# MCU.net
KiCad netlist of a schematic drawn in Altium Designer
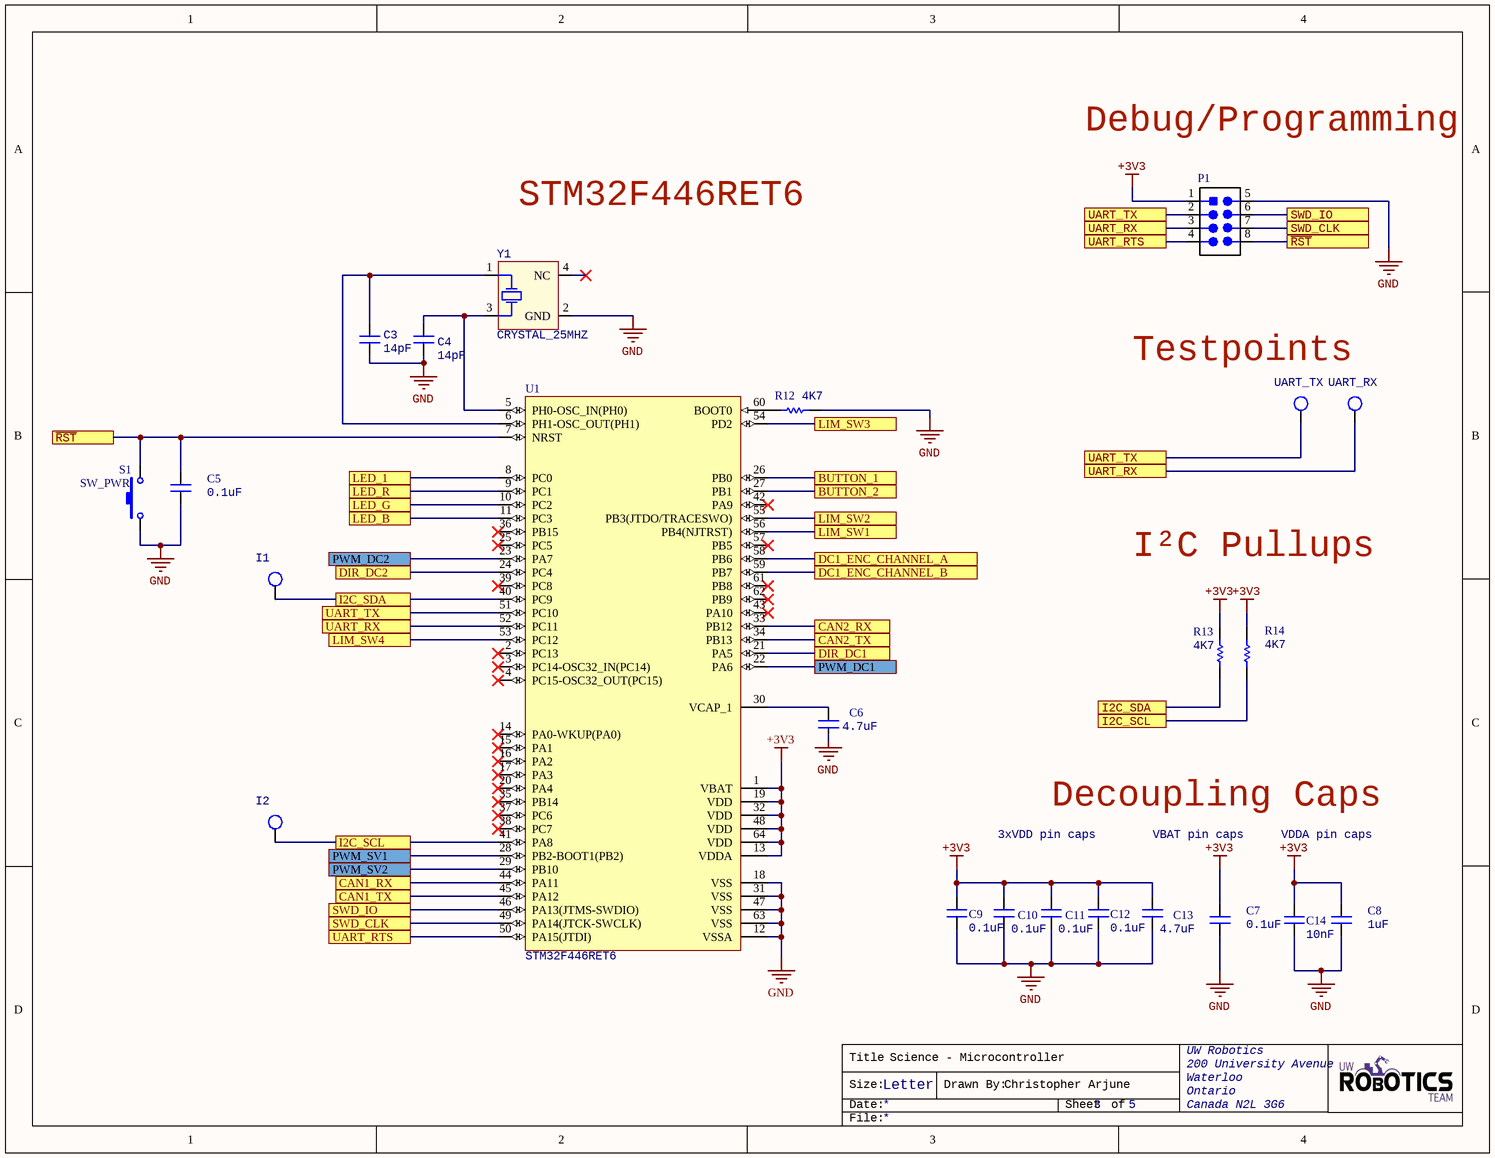
[diagram p0: MCU.SchDoc]

(export (version "E")
  (design (tool "Eeschema 10.0.6"))
  (components
    (comp (ref "C3")
      (value "14pF")
      (description "CAP CER 14PF 50V C0G/NP0 0603")
      (fields (field (name "TOLERANCE") "5%") (field (name "Comment") "CAP_14pF_50V_0603"))
      (libsource (lib "UWRT_Schematic_Library_2020") (part "CAP_14pF_50V_0603"))
    )
    (comp (ref "C4")
      (value "14pF")
      (description "CAP CER 14PF 50V C0G/NP0 0603")
      (fields (field (name "TOLERANCE") "5%") (field (name "Comment") "CAP_14pF_50V_0603"))
      (libsource (lib "UWRT_Schematic_Library_2020") (part "CAP_14pF_50V_0603"))
    )
    (comp (ref "C5")
      (value "0.1uF")
      (footprint "CAPC0603(1608)55_N")
      (description "CAP CER 0.1UF 16V X7R 0603")
      (fields (field (name "MANUFACTURER") "Yageo") (field (name "MPN") "CC0603KRX7R7BB104"))
      (libsource (lib "UWRT_Schematic_Library_2020") (part "CAP_0.1uF_16V_0603"))
    )
    (comp (ref "C6")
      (value "4.7uF")
      (footprint "CAPC0603(1608)55_N")
      (description "CAP CER 4.7UF 6.3V X5R 0603")
      (fields (field (name "MANUFACTURER") "Yageo") (field (name "MPN") "CC0603KRX5R5BB475"))
      (libsource (lib "UWRT_Schematic_Library_2020") (part "CAP_4.7uF_0603"))
    )
    (comp (ref "C7")
      (value "0.1uF")
      (footprint "CAPC0603(1608)55_N")
      (description "CAP CER 0.1UF 16V X7R 0603")
      (fields (field (name "MANUFACTURER") "Yageo") (field (name "MPN") "CC0603KRX7R7BB104"))
      (libsource (lib "UWRT_Schematic_Library_2020") (part "CAP_0.1uF_16V_0603"))
    )
    (comp (ref "C8")
      (value "1uF")
      (footprint "CAPC0603(1608)55_N")
      (description "CAP CER 1UF 16V Y5V 0603")
      (fields (field (name "MANUFACTURER") "Yageo") (field (name "MPN") "CC0603ZRY5V7BB105"))
      (libsource (lib "UWRT_Schematic_Library_2020") (part "CAP_1uF_16V_0603"))
    )
    (comp (ref "C9")
      (value "0.1uF")
      (footprint "CAPC0603(1608)55_N")
      (description "CAP CER 0.1UF 16V X7R 0603")
      (fields (field (name "MANUFACTURER") "Yageo") (field (name "MPN") "CC0603KRX7R7BB104"))
      (libsource (lib "UWRT_Schematic_Library_2020") (part "CAP_0.1uF_16V_0603"))
    )
    (comp (ref "C10")
      (value "0.1uF")
      (footprint "CAPC0603(1608)55_N")
      (description "CAP CER 0.1UF 16V X7R 0603")
      (fields (field (name "MANUFACTURER") "Yageo") (field (name "MPN") "CC0603KRX7R7BB104"))
      (libsource (lib "UWRT_Schematic_Library_2020") (part "CAP_0.1uF_16V_0603"))
    )
    (comp (ref "C11")
      (value "0.1uF")
      (footprint "CAPC0603(1608)55_N")
      (description "CAP CER 0.1UF 16V X7R 0603")
      (fields (field (name "MANUFACTURER") "Yageo") (field (name "MPN") "CC0603KRX7R7BB104"))
      (libsource (lib "UWRT_Schematic_Library_2020") (part "CAP_0.1uF_16V_0603"))
    )
    (comp (ref "C12")
      (value "0.1uF")
      (footprint "CAPC0603(1608)55_N")
      (description "CAP CER 0.1UF 16V X7R 0603")
      (fields (field (name "MANUFACTURER") "Yageo") (field (name "MPN") "CC0603KRX7R7BB104"))
      (libsource (lib "UWRT_Schematic_Library_2020") (part "CAP_0.1uF_16V_0603"))
    )
    (comp (ref "C13")
      (value "4.7uF")
      (footprint "CAPC0603(1608)55_N")
      (description "CAP CER 4.7UF 6.3V X5R 0603")
      (fields (field (name "MANUFACTURER") "Yageo") (field (name "MPN") "CC0603KRX5R5BB475"))
      (libsource (lib "UWRT_Schematic_Library_2020") (part "CAP_4.7uF_0603"))
    )
    (comp (ref "C14")
      (value "10nF")
      (footprint "CAPC0603(1608)55_N")
      (description "CAP CER 10000PF 16V X7R 0603")
      (fields (field (name "MANUFACTURER") "Yageo") (field (name "MPN") "CC0603KRX7R7BB103"))
      (libsource (lib "UWRT_Schematic_Library_2020") (part "CAP_10nF_0603"))
    )
    (comp (ref "I1")
      (value "TESTPOINT_LOOP")
      (footprint "TESTPOINT_LOOP")
      (description "Loop testpoint through-hole pad")
      (fields (field (name "MANUFACTURER") "Keystone Electronics"))
      (libsource (lib "UWRT_Schematic_Library_2020") (part "TESTPOINT_LOOP"))
    )
    (comp (ref "I2")
      (value "TESTPOINT_LOOP")
      (footprint "TESTPOINT_LOOP")
      (description "Loop testpoint through-hole pad")
      (fields (field (name "MANUFACTURER") "Keystone Electronics"))
      (libsource (lib "UWRT_Schematic_Library_2020") (part "TESTPOINT_LOOP"))
    )
    (comp (ref "P1")
      (value "HEADER 4X2")
      (footprint "HEADER_2X4")
      (description "CONN HEADER VERT 8POS 2.54MM")
      (libsource (lib "UWRT_Schematic_Library_2020") (part "HEADER 4X2"))
    )
    (comp (ref "R12")
      (value "4K7")
      (footprint "RESC0603(1608)_N")
      (description "RES SMD 4.7K OHM 5% 1/10W 0603")
      (fields (field (name "MANUFACTURER") "Yageo") (field (name "TOLERANCE") "5%"))
      (libsource (lib "UWRT_Schematic_Library_2020") (part "RES_4K7_0603"))
    )
    (comp (ref "R13")
      (value "4K7")
      (footprint "RESC0603(1608)_N")
      (description "RES SMD 4.7K OHM 5% 1/10W 0603")
      (fields (field (name "MANUFACTURER") "Yageo") (field (name "TOLERANCE") "5%"))
      (libsource (lib "UWRT_Schematic_Library_2020") (part "RES_4K7_0603"))
    )
    (comp (ref "R14")
      (value "4K7")
      (footprint "RESC0603(1608)_N")
      (description "RES SMD 4.7K OHM 5% 1/10W 0603")
      (fields (field (name "MANUFACTURER") "Yageo") (field (name "TOLERANCE") "5%"))
      (libsource (lib "UWRT_Schematic_Library_2020") (part "RES_4K7_0603"))
    )
    (comp (ref "S1")
      (value "SW_PWR")
      (footprint "PTS830GM140")
      (description "Power Switch (Red)")
      (fields (field (name "MPN") "PTS830GM140 SMTR LFS") (field (name "MANUFACTURER") "C&K"))
      (libsource (lib "UWRT_Schematic_Library_2020") (part "SW_PWR"))
    )
    (comp (ref "U1")
      (value "STM32F446RET6")
      (footprint "STM-LQFP64_L")
      (libsource (lib "UWRT_Schematic_Library_2020") (part "MCU_STM32F446RET6"))
    )
    (comp (ref "UART_RX")
      (value "TESTPOINT_LOOP")
      (footprint "TESTPOINT_LOOP")
      (description "Loop testpoint through-hole pad")
      (fields (field (name "MANUFACTURER") "Keystone Electronics"))
      (libsource (lib "UWRT_Schematic_Library_2020") (part "TESTPOINT_LOOP"))
    )
    (comp (ref "UART_TX")
      (value "TESTPOINT_LOOP")
      (footprint "TESTPOINT_LOOP")
      (description "Loop testpoint through-hole pad")
      (fields (field (name "MANUFACTURER") "Keystone Electronics"))
      (libsource (lib "UWRT_Schematic_Library_2020") (part "TESTPOINT_LOOP"))
    )
    (comp (ref "Y1")
      (value "CRYSTAL_25MHZ")
      (description "CRYSTAL 25.0000MHZ 12PF SMD")
      (libsource (lib "UWRT_Schematic_Library_2020") (part "CRYSTAL_25MHZ"))
    )
  )
  (nets
    (net (code "1") (name "+3V3") (class "Default")
      (node (ref "C10") (pin "2") (pinfunction "2_2") (pintype "passive"))
      (node (ref "C11") (pin "2") (pinfunction "2_2") (pintype "passive"))
      (node (ref "C12") (pin "2") (pinfunction "2_2") (pintype "passive"))
      (node (ref "C13") (pin "2") (pinfunction "2_2") (pintype "passive"))
      (node (ref "C14") (pin "2") (pinfunction "2_2") (pintype "passive"))
      (node (ref "C7") (pin "2") (pinfunction "2_2") (pintype "passive"))
      (node (ref "C8") (pin "2") (pinfunction "2_2") (pintype "passive"))
      (node (ref "C9") (pin "2") (pinfunction "2_2") (pintype "passive"))
      (node (ref "P1") (pin "1") (pinfunction "VCC_1") (pintype "passive"))
      (node (ref "R13") (pin "2") (pinfunction "2_2") (pintype "passive"))
      (node (ref "R14") (pin "2") (pinfunction "2_2") (pintype "passive"))
      (node (ref "U1") (pin "1") (pinfunction "VBAT_1") (pintype "power_in"))
      (node (ref "U1") (pin "13") (pinfunction "VDDA_13") (pintype "power_in"))
      (node (ref "U1") (pin "19") (pinfunction "VDD_19") (pintype "power_in"))
      (node (ref "U1") (pin "32") (pinfunction "VDD_32") (pintype "power_in"))
      (node (ref "U1") (pin "48") (pinfunction "VDD_48") (pintype "power_in"))
      (node (ref "U1") (pin "64") (pinfunction "VDD_64") (pintype "power_in"))
    )
    (net (code "2") (name "/BUTTON_1") (class "Default")
      (node (ref "U1") (pin "26") (pinfunction "PB0_26") (pintype "bidirectional"))
    )
    (net (code "3") (name "/BUTTON_2") (class "Default")
      (node (ref "U1") (pin "27") (pinfunction "PB1_27") (pintype "bidirectional"))
    )
    (net (code "4") (name "/CAN1_RX") (class "Default")
      (node (ref "U1") (pin "44") (pinfunction "PA11_44") (pintype "bidirectional"))
    )
    (net (code "5") (name "/CAN1_TX") (class "Default")
      (node (ref "U1") (pin "45") (pinfunction "PA12_45") (pintype "bidirectional"))
    )
    (net (code "6") (name "/CAN2_RX") (class "Default")
      (node (ref "U1") (pin "33") (pinfunction "PB12_33") (pintype "bidirectional"))
    )
    (net (code "7") (name "/CAN2_TX") (class "Default")
      (node (ref "U1") (pin "34") (pinfunction "PB13_34") (pintype "bidirectional"))
    )
    (net (code "8") (name "/DC1_ENC_CHANNEL_A") (class "Default")
      (node (ref "U1") (pin "58") (pinfunction "PB6_58") (pintype "bidirectional"))
    )
    (net (code "9") (name "/DC1_ENC_CHANNEL_B") (class "Default")
      (node (ref "U1") (pin "59") (pinfunction "PB7_59") (pintype "bidirectional"))
    )
    (net (code "10") (name "/DIR_DC1") (class "Default")
      (node (ref "U1") (pin "21") (pinfunction "PA5_21") (pintype "bidirectional"))
    )
    (net (code "11") (name "/DIR_DC2") (class "Default")
      (node (ref "U1") (pin "24") (pinfunction "PC4_24") (pintype "bidirectional"))
    )
    (net (code "12") (name "/I2C_SCL") (class "Default")
      (node (ref "I2") (pin "1") (pintype "passive"))
      (node (ref "R14") (pin "1") (pinfunction "1_1") (pintype "passive"))
      (node (ref "U1") (pin "41") (pinfunction "PA8_41") (pintype "bidirectional"))
    )
    (net (code "13") (name "/I2C_SDA") (class "Default")
      (node (ref "I1") (pin "1") (pintype "passive"))
      (node (ref "R13") (pin "1") (pinfunction "1_1") (pintype "passive"))
      (node (ref "U1") (pin "40") (pinfunction "PC9_40") (pintype "bidirectional"))
    )
    (net (code "14") (name "/LED_1") (class "Default")
      (node (ref "U1") (pin "8") (pinfunction "PC0_8") (pintype "bidirectional"))
    )
    (net (code "15") (name "/LED_B") (class "Default")
      (node (ref "U1") (pin "11") (pinfunction "PC3_11") (pintype "bidirectional"))
    )
    (net (code "16") (name "/LED_G") (class "Default")
      (node (ref "U1") (pin "10") (pinfunction "PC2_10") (pintype "bidirectional"))
    )
    (net (code "17") (name "/LED_R") (class "Default")
      (node (ref "U1") (pin "9") (pinfunction "PC1_9") (pintype "bidirectional"))
    )
    (net (code "18") (name "/LIM_SW1") (class "Default")
      (node (ref "U1") (pin "56") (pinfunction "PB4(NJTRST)_56") (pintype "bidirectional"))
    )
    (net (code "19") (name "/LIM_SW2") (class "Default")
      (node (ref "U1") (pin "55") (pinfunction "PB3(JTDO/TRACESWO)_55") (pintype "bidirectional"))
    )
    (net (code "20") (name "/LIM_SW3") (class "Default")
      (node (ref "U1") (pin "54") (pinfunction "PD2_54") (pintype "bidirectional"))
    )
    (net (code "21") (name "/LIM_SW4") (class "Default")
      (node (ref "U1") (pin "53") (pinfunction "PC12_53") (pintype "bidirectional"))
    )
    (net (code "22") (name "/PWM_DC1") (class "Default")
      (node (ref "U1") (pin "22") (pinfunction "PA6_22") (pintype "bidirectional"))
    )
    (net (code "23") (name "/PWM_DC2") (class "Default")
      (node (ref "U1") (pin "23") (pinfunction "PA7_23") (pintype "bidirectional"))
    )
    (net (code "24") (name "/PWM_SV1") (class "Default")
      (node (ref "U1") (pin "28") (pinfunction "PB2-BOOT1(PB2)_28") (pintype "bidirectional"))
    )
    (net (code "25") (name "/PWM_SV2") (class "Default")
      (node (ref "U1") (pin "29") (pinfunction "PB10_29") (pintype "bidirectional"))
    )
    (net (code "26") (name "/SWD_CLK") (class "Default")
      (node (ref "P1") (pin "7") (pinfunction "3_7") (pintype "passive"))
      (node (ref "U1") (pin "49") (pinfunction "PA14(JTCK-SWCLK)_49") (pintype "bidirectional"))
    )
    (net (code "27") (name "/SWD_IO") (class "Default")
      (node (ref "P1") (pin "6") (pinfunction "2_6") (pintype "passive"))
      (node (ref "U1") (pin "46") (pinfunction "PA13(JTMS-SWDIO)_46") (pintype "bidirectional"))
    )
    (net (code "28") (name "/UART_RTS") (class "Default")
      (node (ref "P1") (pin "4") (pinfunction "4_4") (pintype "passive"))
      (node (ref "U1") (pin "50") (pinfunction "PA15(JTDI)_50") (pintype "bidirectional"))
    )
    (net (code "29") (name "/UART_RX") (class "Default")
      (node (ref "P1") (pin "3") (pinfunction "3_3") (pintype "passive"))
      (node (ref "U1") (pin "52") (pinfunction "PC11_52") (pintype "bidirectional"))
      (node (ref "UART_RX") (pin "1") (pintype "passive"))
    )
    (net (code "30") (name "/UART_TX") (class "Default")
      (node (ref "P1") (pin "2") (pinfunction "2_2") (pintype "passive"))
      (node (ref "U1") (pin "51") (pinfunction "PC10_51") (pintype "bidirectional"))
      (node (ref "UART_TX") (pin "1") (pintype "passive"))
    )
    (net (code "31") (name "/~{RST}") (class "Default")
      (node (ref "C5") (pin "2") (pinfunction "2_2") (pintype "passive"))
      (node (ref "P1") (pin "8") (pinfunction "4_8") (pintype "passive"))
      (node (ref "S1") (pin "2") (pinfunction "2_2") (pintype "passive"))
      (node (ref "U1") (pin "7") (pinfunction "NRST_7") (pintype "bidirectional"))
    )
    (net (code "32") (name "GND") (class "Default")
      (node (ref "C10") (pin "1") (pinfunction "1_1") (pintype "passive"))
      (node (ref "C11") (pin "1") (pinfunction "1_1") (pintype "passive"))
      (node (ref "C12") (pin "1") (pinfunction "1_1") (pintype "passive"))
      (node (ref "C13") (pin "1") (pinfunction "1_1") (pintype "passive"))
      (node (ref "C14") (pin "1") (pinfunction "1_1") (pintype "passive"))
      (node (ref "C3") (pin "1") (pinfunction "1_1") (pintype "passive"))
      (node (ref "C4") (pin "1") (pinfunction "1_1") (pintype "passive"))
      (node (ref "C5") (pin "1") (pinfunction "1_1") (pintype "passive"))
      (node (ref "C6") (pin "1") (pinfunction "1_1") (pintype "passive"))
      (node (ref "C7") (pin "1") (pinfunction "1_1") (pintype "passive"))
      (node (ref "C8") (pin "1") (pinfunction "1_1") (pintype "passive"))
      (node (ref "C9") (pin "1") (pinfunction "1_1") (pintype "passive"))
      (node (ref "P1") (pin "5") (pinfunction "GND_5") (pintype "passive"))
      (node (ref "R12") (pin "1") (pinfunction "1_1") (pintype "passive"))
      (node (ref "S1") (pin "1") (pinfunction "1_1") (pintype "passive"))
      (node (ref "U1") (pin "12") (pinfunction "VSSA_12") (pintype "power_in"))
      (node (ref "U1") (pin "18") (pinfunction "VSS_18") (pintype "power_in"))
      (node (ref "U1") (pin "31") (pinfunction "VSS_31") (pintype "power_in"))
      (node (ref "U1") (pin "47") (pinfunction "VSS_47") (pintype "power_in"))
      (node (ref "U1") (pin "63") (pinfunction "VSS_63") (pintype "power_in"))
      (node (ref "Y1") (pin "2") (pinfunction "GND_2") (pintype "power_in"))
    )
    (net (code "33") (name "Net-(U1-BOOT0)") (class "Default")
      (node (ref "R12") (pin "2") (pinfunction "2_2") (pintype "passive"))
      (node (ref "U1") (pin "60") (pinfunction "BOOT0_60") (pintype "input"))
    )
    (net (code "34") (name "Net-(U1-PH0-OSC_IN(PH0))") (class "Default")
      (node (ref "C4") (pin "2") (pinfunction "2_2") (pintype "passive"))
      (node (ref "U1") (pin "5") (pinfunction "PH0-OSC_IN(PH0)_5") (pintype "bidirectional"))
      (node (ref "Y1") (pin "3") (pinfunction "HOT_3") (pintype "passive"))
    )
    (net (code "35") (name "Net-(U1-PH1-OSC_OUT(PH1))") (class "Default")
      (node (ref "C3") (pin "2") (pinfunction "2_2") (pintype "passive"))
      (node (ref "U1") (pin "6") (pinfunction "PH1-OSC_OUT(PH1)_6") (pintype "bidirectional"))
      (node (ref "Y1") (pin "1") (pinfunction "HOT_1") (pintype "passive"))
    )
    (net (code "36") (name "Net-(U1-VCAP_1)") (class "Default")
      (node (ref "C6") (pin "2") (pinfunction "2_2") (pintype "passive"))
      (node (ref "U1") (pin "30") (pinfunction "VCAP_1_30") (pintype "passive"))
    )
    (net (code "37") (name "unconnected-(U1-PA0-WKUP(PA0)-Pad14)") (class "Default")
      (node (ref "U1") (pin "14") (pinfunction "PA0-WKUP(PA0)_14") (pintype "bidirectional+no_connect"))
    )
    (net (code "38") (name "unconnected-(U1-PA1-Pad15)") (class "Default")
      (node (ref "U1") (pin "15") (pinfunction "PA1_15") (pintype "bidirectional+no_connect"))
    )
    (net (code "39") (name "unconnected-(U1-PA2-Pad16)") (class "Default")
      (node (ref "U1") (pin "16") (pinfunction "PA2_16") (pintype "bidirectional+no_connect"))
    )
    (net (code "40") (name "unconnected-(U1-PA3-Pad17)") (class "Default")
      (node (ref "U1") (pin "17") (pinfunction "PA3_17") (pintype "bidirectional+no_connect"))
    )
    (net (code "41") (name "unconnected-(U1-PA4-Pad20)") (class "Default")
      (node (ref "U1") (pin "20") (pinfunction "PA4_20") (pintype "bidirectional+no_connect"))
    )
    (net (code "42") (name "unconnected-(U1-PA9-Pad42)") (class "Default")
      (node (ref "U1") (pin "42") (pinfunction "PA9_42") (pintype "bidirectional+no_connect"))
    )
    (net (code "43") (name "unconnected-(U1-PA10-Pad43)") (class "Default")
      (node (ref "U1") (pin "43") (pinfunction "PA10_43") (pintype "bidirectional+no_connect"))
    )
    (net (code "44") (name "unconnected-(U1-PB5-Pad57)") (class "Default")
      (node (ref "U1") (pin "57") (pinfunction "PB5_57") (pintype "bidirectional+no_connect"))
    )
    (net (code "45") (name "unconnected-(U1-PB8-Pad61)") (class "Default")
      (node (ref "U1") (pin "61") (pinfunction "PB8_61") (pintype "bidirectional+no_connect"))
    )
    (net (code "46") (name "unconnected-(U1-PB9-Pad62)") (class "Default")
      (node (ref "U1") (pin "62") (pinfunction "PB9_62") (pintype "bidirectional+no_connect"))
    )
    (net (code "47") (name "unconnected-(U1-PB14-Pad35)") (class "Default")
      (node (ref "U1") (pin "35") (pinfunction "PB14_35") (pintype "bidirectional+no_connect"))
    )
    (net (code "48") (name "unconnected-(U1-PB15-Pad36)") (class "Default")
      (node (ref "U1") (pin "36") (pinfunction "PB15_36") (pintype "bidirectional+no_connect"))
    )
    (net (code "49") (name "unconnected-(U1-PC5-Pad25)") (class "Default")
      (node (ref "U1") (pin "25") (pinfunction "PC5_25") (pintype "bidirectional+no_connect"))
    )
    (net (code "50") (name "unconnected-(U1-PC6-Pad37)") (class "Default")
      (node (ref "U1") (pin "37") (pinfunction "PC6_37") (pintype "bidirectional+no_connect"))
    )
    (net (code "51") (name "unconnected-(U1-PC7-Pad38)") (class "Default")
      (node (ref "U1") (pin "38") (pinfunction "PC7_38") (pintype "bidirectional+no_connect"))
    )
    (net (code "52") (name "unconnected-(U1-PC8-Pad39)") (class "Default")
      (node (ref "U1") (pin "39") (pinfunction "PC8_39") (pintype "bidirectional+no_connect"))
    )
    (net (code "53") (name "unconnected-(U1-PC13-Pad2)") (class "Default")
      (node (ref "U1") (pin "2") (pinfunction "PC13_2") (pintype "bidirectional+no_connect"))
    )
    (net (code "54") (name "unconnected-(U1-PC14-OSC32_IN(PC14)-Pad3)") (class "Default")
      (node (ref "U1") (pin "3") (pinfunction "PC14-OSC32_IN(PC14)_3") (pintype "bidirectional+no_connect"))
    )
    (net (code "55") (name "unconnected-(U1-PC15-OSC32_OUT(PC15)-Pad4)") (class "Default")
      (node (ref "U1") (pin "4") (pinfunction "PC15-OSC32_OUT(PC15)_4") (pintype "bidirectional+no_connect"))
    )
    (net (code "56") (name "unconnected-(Y1-NC-Pad4)") (class "Default")
      (node (ref "Y1") (pin "4") (pinfunction "NC_4") (pintype "passive+no_connect"))
    )
  )
)
